# PIR_AM612_pro_hodiny.net
KiCad netlist of a schematic drawn in EAGLE
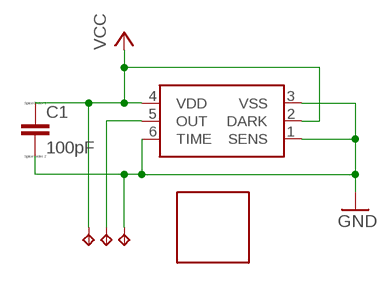
[diagram p0: schematic, sheet 1]

(export (version "E")
  (design (tool "Eeschema 10.0.6"))
  (components
    (comp (ref "C1")
      (value "100pF")
      (footprint "eagle-import:C0603")
      (libsource (lib "eagle-import") (part "CC0603"))
    )
    (comp (ref "TP1")
      (value "TPB1,27")
      (footprint "eagle-import:B1,27")
      (libsource (lib "eagle-import") (part "TPB1,27"))
    )
    (comp (ref "TP2")
      (value "TPB1,27")
      (footprint "eagle-import:B1,27")
      (libsource (lib "eagle-import") (part "TPB1,27"))
    )
    (comp (ref "TP3")
      (value "TPB1,27")
      (footprint "eagle-import:B1,27")
      (libsource (lib "eagle-import") (part "TPB1,27"))
    )
    (comp (ref "U$1")
      (value "AM612")
      (footprint "eagle-import:TO5")
      (libsource (lib "eagle-import") (part "AM612"))
    )
    (comp (ref "U$2")
      (value "LOGO_VOKOLO7,5MM")
      (footprint "eagle-import:LOGO_VOKOLO_6,2MM")
      (libsource (lib "eagle-import") (part "LOGO_VOKOLO7,5MM"))
    )
  )
  (nets
    (net (code "1") (name "GND") (class "Default")
      (node (ref "C1") (pin "2") (pinfunction "2_2") (pintype "passive"))
      (node (ref "TP3") (pin "TP") (pinfunction "TP_TP") (pintype "input"))
      (node (ref "U$1") (pin "1") (pinfunction "SENS_1") (pintype "bidirectional"))
      (node (ref "U$1") (pin "3") (pinfunction "VSS_3") (pintype "bidirectional"))
      (node (ref "U$1") (pin "6") (pinfunction "TIME_6") (pintype "bidirectional"))
    )
    (net (code "2") (name "Net-(U$1-OUT)") (class "Default")
      (node (ref "TP2") (pin "TP") (pinfunction "TP_TP") (pintype "input"))
      (node (ref "U$1") (pin "5") (pinfunction "OUT_5") (pintype "bidirectional"))
    )
    (net (code "3") (name "VCC") (class "Default")
      (node (ref "C1") (pin "1") (pinfunction "1_1") (pintype "passive"))
      (node (ref "TP1") (pin "TP") (pinfunction "TP_TP") (pintype "input"))
      (node (ref "U$1") (pin "2") (pinfunction "DARK_2") (pintype "bidirectional"))
      (node (ref "U$1") (pin "4") (pinfunction "VDD_4") (pintype "bidirectional"))
    )
  )
)
